# board.net
KiCad netlist of a schematic drawn in EAGLE
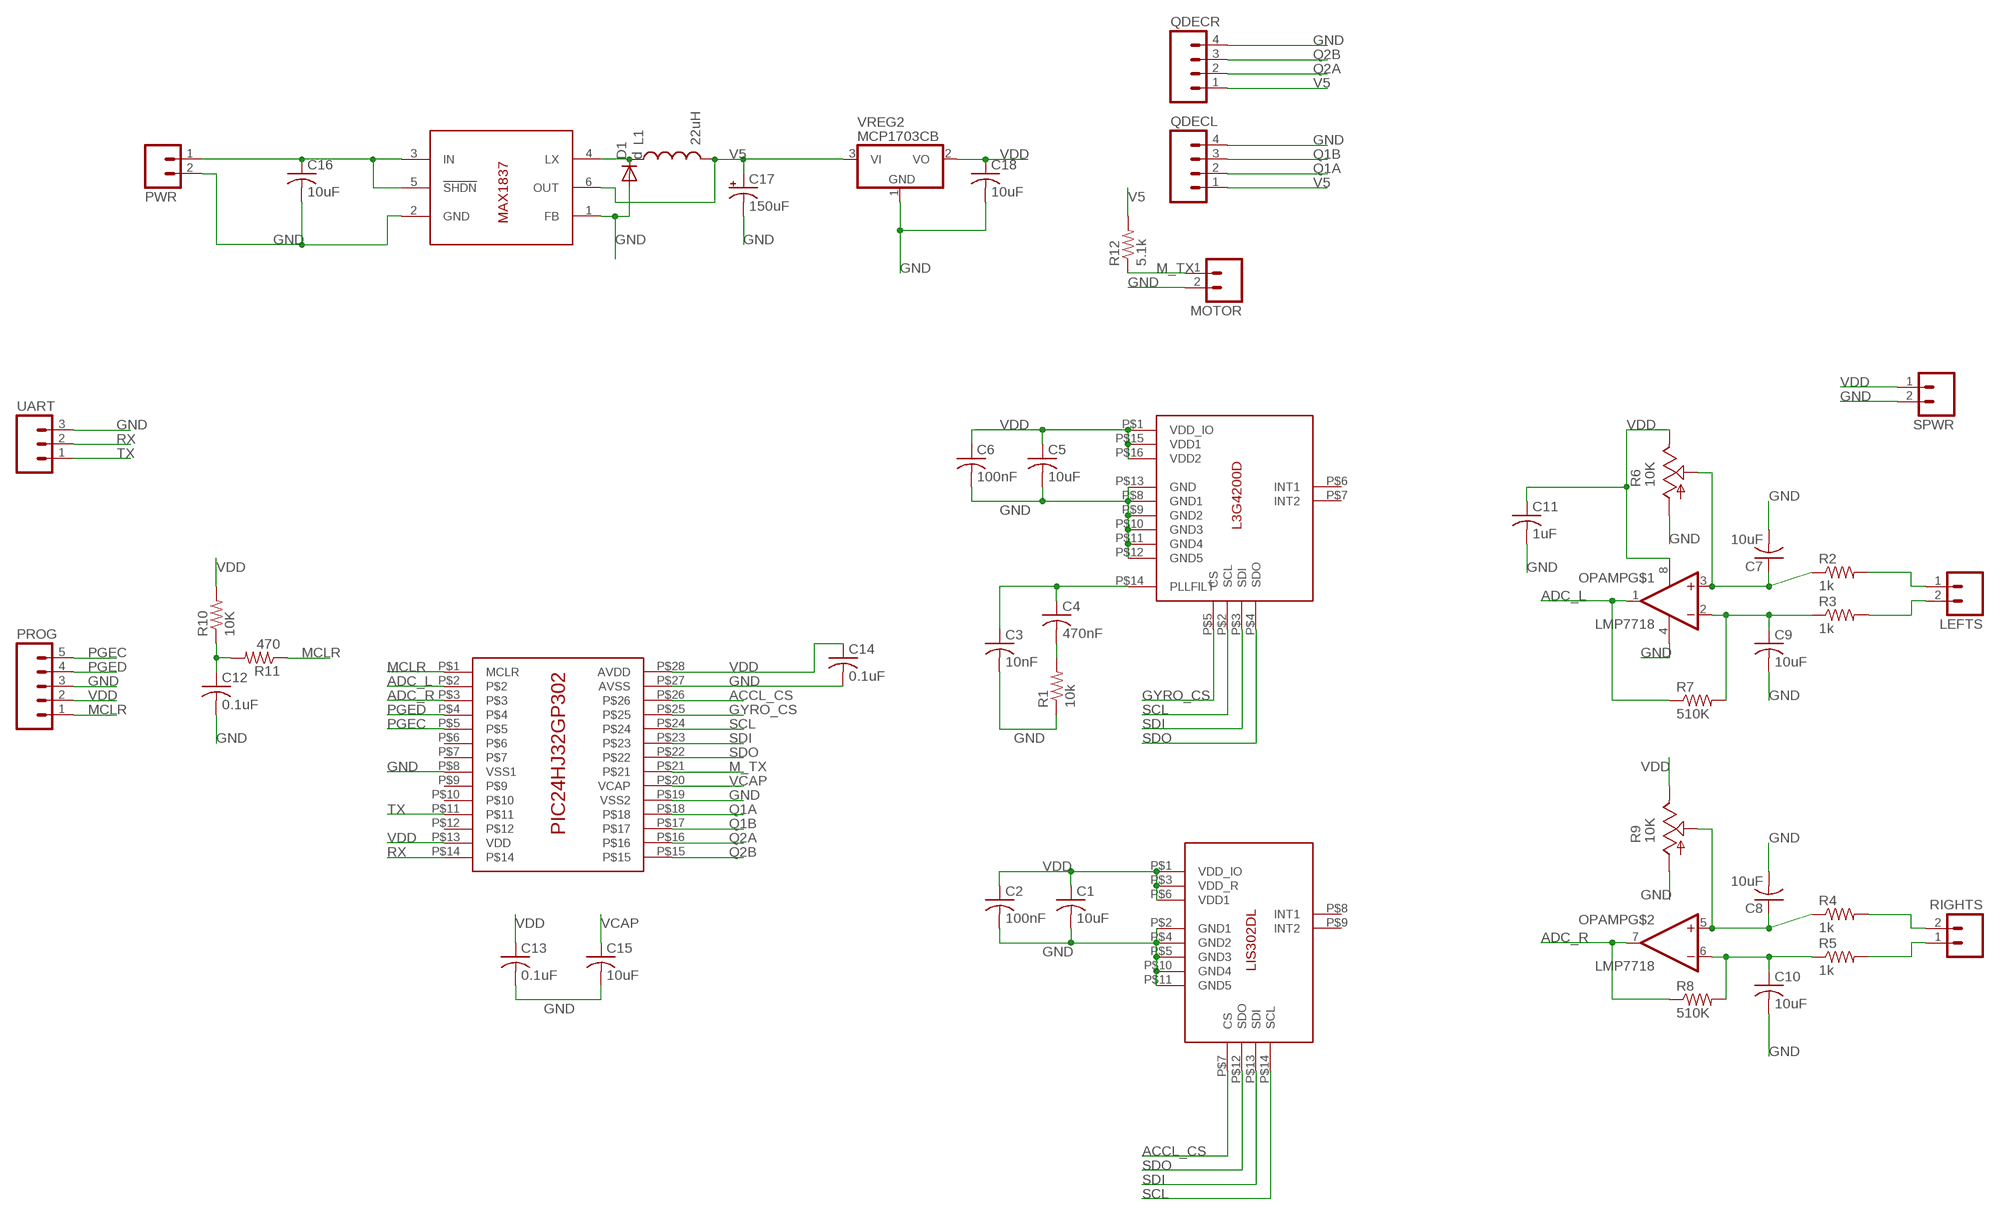
[diagram p0: schematic, sheet 1]

(export (version "E")
  (design (tool "Eeschema 10.0.6"))
  (components
    (comp (ref "C1")
      (value "10uF")
      (footprint "eagle-import:C0805")
      (libsource (lib "eagle-import") (part "C-USC0805"))
    )
    (comp (ref "C2")
      (value "100nF")
      (footprint "eagle-import:C0805")
      (libsource (lib "eagle-import") (part "C-USC0805"))
    )
    (comp (ref "C3")
      (value "10nF")
      (footprint "eagle-import:C0805")
      (libsource (lib "eagle-import") (part "C-USC0805"))
    )
    (comp (ref "C4")
      (value "470nF")
      (footprint "eagle-import:C0805")
      (libsource (lib "eagle-import") (part "C-USC0805"))
    )
    (comp (ref "C5")
      (value "10uF")
      (footprint "eagle-import:C0805")
      (libsource (lib "eagle-import") (part "C-USC0805"))
    )
    (comp (ref "C6")
      (value "100nF")
      (footprint "eagle-import:C0805")
      (libsource (lib "eagle-import") (part "C-USC0805"))
    )
    (comp (ref "C7")
      (value "10uF")
      (footprint "eagle-import:C1206")
      (libsource (lib "eagle-import") (part "C-USC1206"))
    )
    (comp (ref "C8")
      (value "10uF")
      (footprint "eagle-import:C1206")
      (libsource (lib "eagle-import") (part "C-USC1206"))
    )
    (comp (ref "C9")
      (value "10uF")
      (footprint "eagle-import:C1206")
      (libsource (lib "eagle-import") (part "C-USC1206"))
    )
    (comp (ref "C10")
      (value "10uF")
      (footprint "eagle-import:C1206")
      (libsource (lib "eagle-import") (part "C-USC1206"))
    )
    (comp (ref "C11")
      (value "1uF")
      (footprint "eagle-import:C0805")
      (libsource (lib "eagle-import") (part "C-USC0805"))
    )
    (comp (ref "C12")
      (value "0.1uF")
      (footprint "eagle-import:C0805")
      (libsource (lib "eagle-import") (part "C-USC0805"))
    )
    (comp (ref "C13")
      (value "0.1uF")
      (footprint "eagle-import:C0805")
      (libsource (lib "eagle-import") (part "C-USC0805"))
    )
    (comp (ref "C14")
      (value "0.1uF")
      (footprint "eagle-import:C0805")
      (libsource (lib "eagle-import") (part "C-USC0805"))
    )
    (comp (ref "C15")
      (value "10uF")
      (footprint "eagle-import:C0805")
      (libsource (lib "eagle-import") (part "C-USC0805"))
    )
    (comp (ref "C16")
      (value "10uF")
      (footprint "eagle-import:C1206")
      (libsource (lib "eagle-import") (part "C-USC1206"))
    )
    (comp (ref "C17")
      (value "150uF")
      (footprint "eagle-import:CT3528")
      (libsource (lib "eagle-import") (part "CPOL-USCT3528"))
    )
    (comp (ref "C18")
      (value "10uF")
      (footprint "eagle-import:C0805")
      (libsource (lib "eagle-import") (part "C-USC0805"))
    )
    (comp (ref "D1")
      (value "d")
      (footprint "eagle-import:SOD-323")
      (libsource (lib "eagle-import") (part "DIODESOD"))
    )
    (comp (ref "L1")
      (value "22uH")
      (footprint "eagle-import:1007")
      (libsource (lib "eagle-import") (part "INDUCTOR1007"))
    )
    (comp (ref "LEFTS")
      (value "M02POLAR")
      (footprint "eagle-import:MOLEX-1X2")
      (libsource (lib "eagle-import") (part "M02POLAR"))
    )
    (comp (ref "MOTOR")
      (value "M02POLAR")
      (footprint "eagle-import:MOLEX-1X2")
      (libsource (lib "eagle-import") (part "M02POLAR"))
    )
    (comp (ref "OPAMP")
      (value "LMP7718")
      (footprint "eagle-import:SO08")
      (libsource (lib "eagle-import") (part "LMP7718"))
    )
    (comp (ref "PROG")
      (value "M05PTH")
      (footprint "eagle-import:1X05")
      (libsource (lib "eagle-import") (part "M05PTH"))
    )
    (comp (ref "PWR")
      (value "M02POLAR")
      (footprint "eagle-import:MOLEX-1X2")
      (libsource (lib "eagle-import") (part "M02POLAR"))
    )
    (comp (ref "QDECL")
      (value "M04POLAR")
      (footprint "eagle-import:MOLEX-1X4")
      (libsource (lib "eagle-import") (part "M04POLAR"))
    )
    (comp (ref "QDECR")
      (value "M04POLAR")
      (footprint "eagle-import:MOLEX-1X4")
      (libsource (lib "eagle-import") (part "M04POLAR"))
    )
    (comp (ref "R1")
      (value "10k")
      (footprint "eagle-import:R0805")
      (libsource (lib "eagle-import") (part "R-US_R0805"))
    )
    (comp (ref "R2")
      (value "1k")
      (footprint "eagle-import:R1206")
      (libsource (lib "eagle-import") (part "R-US_R1206"))
    )
    (comp (ref "R3")
      (value "1k")
      (footprint "eagle-import:R1206")
      (libsource (lib "eagle-import") (part "R-US_R1206"))
    )
    (comp (ref "R4")
      (value "1k")
      (footprint "eagle-import:R1206")
      (libsource (lib "eagle-import") (part "R-US_R1206"))
    )
    (comp (ref "R5")
      (value "1k")
      (footprint "eagle-import:R1206")
      (libsource (lib "eagle-import") (part "R-US_R1206"))
    )
    (comp (ref "R6")
      (value "10K")
      (footprint "eagle-import:RJ6S")
      (libsource (lib "eagle-import") (part "TRIM_US-RJ6S"))
    )
    (comp (ref "R7")
      (value "510K")
      (footprint "eagle-import:R0805")
      (libsource (lib "eagle-import") (part "R-US_R0805"))
    )
    (comp (ref "R8")
      (value "510K")
      (footprint "eagle-import:R0805")
      (libsource (lib "eagle-import") (part "R-US_R0805"))
    )
    (comp (ref "R9")
      (value "10K")
      (footprint "eagle-import:RJ6S")
      (libsource (lib "eagle-import") (part "TRIM_US-RJ6S"))
    )
    (comp (ref "R10")
      (value "10K")
      (footprint "eagle-import:R0805")
      (libsource (lib "eagle-import") (part "R-US_R0805"))
    )
    (comp (ref "R11")
      (value "470")
      (footprint "eagle-import:R0805")
      (libsource (lib "eagle-import") (part "R-US_R0805"))
    )
    (comp (ref "R12")
      (value "5.1k")
      (footprint "eagle-import:R0805")
      (libsource (lib "eagle-import") (part "R-US_R0805"))
    )
    (comp (ref "RIGHTS")
      (value "M02POLAR")
      (footprint "eagle-import:MOLEX-1X2")
      (libsource (lib "eagle-import") (part "M02POLAR"))
    )
    (comp (ref "SPWR")
      (value "M02POLAR")
      (footprint "eagle-import:MOLEX-1X2")
      (libsource (lib "eagle-import") (part "M02POLAR"))
    )
    (comp (ref "U$1")
      (value "PIC24HJ32GP302")
      (footprint "eagle-import:SOIC-28")
      (libsource (lib "eagle-import") (part "PIC24HJ32GP302"))
    )
    (comp (ref "U$2")
      (value "L3G4200D")
      (footprint "eagle-import:LGA-16")
      (libsource (lib "eagle-import") (part "L3G4200D"))
    )
    (comp (ref "U$3")
      (value "LIS302DL")
      (footprint "eagle-import:LGA-14")
      (libsource (lib "eagle-import") (part "LIS302DL"))
    )
    (comp (ref "UART")
      (value "M03PTH")
      (footprint "eagle-import:1X03")
      (libsource (lib "eagle-import") (part "M03PTH"))
    )
    (comp (ref "VREG1")
      (value "MAX1837")
      (footprint "eagle-import:SOT23-6L")
      (libsource (lib "eagle-import") (part "MAX1837"))
    )
    (comp (ref "VREG2")
      (value "MCP1703CB")
      (footprint "eagle-import:SOT23")
      (libsource (lib "eagle-import") (part "MCP1703CB"))
    )
  )
  (nets
    (net (code "1") (name "/ACCL_CS") (class "Default")
      (node (ref "U$1") (pin "P$26") (pinfunction "P$26_P$26") (pintype "bidirectional"))
      (node (ref "U$3") (pin "P$7") (pinfunction "CS_P$7") (pintype "input"))
    )
    (net (code "2") (name "/ADC_L") (class "Default")
      (node (ref "OPAMP") (pin "1") (pinfunction "OUT_1") (pintype "output"))
      (node (ref "R7") (pin "1") (pinfunction "1_1") (pintype "passive"))
      (node (ref "U$1") (pin "P$2") (pinfunction "P$2_P$2") (pintype "bidirectional"))
    )
    (net (code "3") (name "/ADC_R") (class "Default")
      (node (ref "OPAMP") (pin "7") (pinfunction "OUT_7") (pintype "output"))
      (node (ref "R8") (pin "1") (pinfunction "1_1") (pintype "passive"))
      (node (ref "U$1") (pin "P$3") (pinfunction "P$3_P$3") (pintype "bidirectional"))
    )
    (net (code "4") (name "/GND") (class "Default")
      (node (ref "C1") (pin "2") (pinfunction "2_2") (pintype "passive"))
      (node (ref "C10") (pin "2") (pinfunction "2_2") (pintype "passive"))
      (node (ref "C11") (pin "2") (pinfunction "2_2") (pintype "passive"))
      (node (ref "C12") (pin "2") (pinfunction "2_2") (pintype "passive"))
      (node (ref "C13") (pin "2") (pinfunction "2_2") (pintype "passive"))
      (node (ref "C14") (pin "2") (pinfunction "2_2") (pintype "passive"))
      (node (ref "C15") (pin "2") (pinfunction "2_2") (pintype "passive"))
      (node (ref "C16") (pin "2") (pinfunction "2_2") (pintype "passive"))
      (node (ref "C17") (pin "-") (pinfunction "-_-") (pintype "passive"))
      (node (ref "C18") (pin "2") (pinfunction "2_2") (pintype "passive"))
      (node (ref "C2") (pin "2") (pinfunction "2_2") (pintype "passive"))
      (node (ref "C3") (pin "2") (pinfunction "2_2") (pintype "passive"))
      (node (ref "C5") (pin "2") (pinfunction "2_2") (pintype "passive"))
      (node (ref "C6") (pin "2") (pinfunction "2_2") (pintype "passive"))
      (node (ref "C7") (pin "2") (pinfunction "2_2") (pintype "passive"))
      (node (ref "C8") (pin "2") (pinfunction "2_2") (pintype "passive"))
      (node (ref "C9") (pin "2") (pinfunction "2_2") (pintype "passive"))
      (node (ref "D1") (pin "2") (pinfunction "A_2") (pintype "passive"))
      (node (ref "MOTOR") (pin "2") (pinfunction "2_2") (pintype "passive"))
      (node (ref "OPAMP") (pin "4") (pinfunction "V-_4") (pintype "power_in"))
      (node (ref "PROG") (pin "3") (pinfunction "3_3") (pintype "passive"))
      (node (ref "PWR") (pin "2") (pinfunction "2_2") (pintype "passive"))
      (node (ref "QDECL") (pin "4") (pinfunction "4_4") (pintype "passive"))
      (node (ref "QDECR") (pin "4") (pinfunction "4_4") (pintype "passive"))
      (node (ref "R1") (pin "1") (pinfunction "1_1") (pintype "passive"))
      (node (ref "R6") (pin "A") (pinfunction "A_A") (pintype "passive"))
      (node (ref "R9") (pin "A") (pinfunction "A_A") (pintype "passive"))
      (node (ref "SPWR") (pin "2") (pinfunction "2_2") (pintype "passive"))
      (node (ref "U$1") (pin "P$19") (pinfunction "VSS2_P$19") (pintype "power_in"))
      (node (ref "U$1") (pin "P$27") (pinfunction "AVSS_P$27") (pintype "power_in"))
      (node (ref "U$1") (pin "P$8") (pinfunction "VSS1_P$8") (pintype "power_in"))
      (node (ref "U$2") (pin "P$10") (pinfunction "GND3_P$10") (pintype "power_in"))
      (node (ref "U$2") (pin "P$11") (pinfunction "GND4_P$11") (pintype "power_in"))
      (node (ref "U$2") (pin "P$12") (pinfunction "GND5_P$12") (pintype "power_in"))
      (node (ref "U$2") (pin "P$13") (pinfunction "GND_P$13") (pintype "power_in"))
      (node (ref "U$2") (pin "P$8") (pinfunction "GND1_P$8") (pintype "power_in"))
      (node (ref "U$2") (pin "P$9") (pinfunction "GND2_P$9") (pintype "power_in"))
      (node (ref "U$3") (pin "P$10") (pinfunction "GND4_P$10") (pintype "power_in"))
      (node (ref "U$3") (pin "P$11") (pinfunction "GND5_P$11") (pintype "power_in"))
      (node (ref "U$3") (pin "P$2") (pinfunction "GND1_P$2") (pintype "power_in"))
      (node (ref "U$3") (pin "P$4") (pinfunction "GND2_P$4") (pintype "power_in"))
      (node (ref "U$3") (pin "P$5") (pinfunction "GND3_P$5") (pintype "power_in"))
      (node (ref "UART") (pin "3") (pinfunction "3_3") (pintype "passive"))
      (node (ref "VREG1") (pin "1") (pinfunction "FB_1") (pintype "input"))
      (node (ref "VREG1") (pin "2") (pinfunction "GND_2") (pintype "power_in"))
      (node (ref "VREG2") (pin "1") (pinfunction "GND_1") (pintype "passive"))
    )
    (net (code "5") (name "/GYRO_CS") (class "Default")
      (node (ref "U$1") (pin "P$25") (pinfunction "P$25_P$25") (pintype "bidirectional"))
      (node (ref "U$2") (pin "P$5") (pinfunction "CS_P$5") (pintype "input"))
    )
    (net (code "6") (name "/MCLR") (class "Default")
      (node (ref "PROG") (pin "1") (pinfunction "1_1") (pintype "passive"))
      (node (ref "R11") (pin "1") (pinfunction "1_1") (pintype "passive"))
      (node (ref "U$1") (pin "P$1") (pinfunction "MCLR_P$1") (pintype "input"))
    )
    (net (code "7") (name "/M_TX") (class "Default")
      (node (ref "MOTOR") (pin "1") (pinfunction "1_1") (pintype "passive"))
      (node (ref "R12") (pin "1") (pinfunction "1_1") (pintype "passive"))
      (node (ref "U$1") (pin "P$21") (pinfunction "P$21_P$21") (pintype "bidirectional"))
    )
    (net (code "8") (name "/PGEC") (class "Default")
      (node (ref "PROG") (pin "5") (pinfunction "5_5") (pintype "passive"))
      (node (ref "U$1") (pin "P$5") (pinfunction "P$5_P$5") (pintype "bidirectional"))
    )
    (net (code "9") (name "/PGED") (class "Default")
      (node (ref "PROG") (pin "4") (pinfunction "4_4") (pintype "passive"))
      (node (ref "U$1") (pin "P$4") (pinfunction "P$4_P$4") (pintype "bidirectional"))
    )
    (net (code "10") (name "/Q1A") (class "Default")
      (node (ref "QDECL") (pin "2") (pinfunction "2_2") (pintype "passive"))
      (node (ref "U$1") (pin "P$18") (pinfunction "P$18_P$18") (pintype "bidirectional"))
    )
    (net (code "11") (name "/Q1B") (class "Default")
      (node (ref "QDECL") (pin "3") (pinfunction "3_3") (pintype "passive"))
      (node (ref "U$1") (pin "P$17") (pinfunction "P$17_P$17") (pintype "bidirectional"))
    )
    (net (code "12") (name "/Q2A") (class "Default")
      (node (ref "QDECR") (pin "2") (pinfunction "2_2") (pintype "passive"))
      (node (ref "U$1") (pin "P$16") (pinfunction "P$16_P$16") (pintype "bidirectional"))
    )
    (net (code "13") (name "/Q2B") (class "Default")
      (node (ref "QDECR") (pin "3") (pinfunction "3_3") (pintype "passive"))
      (node (ref "U$1") (pin "P$15") (pinfunction "P$15_P$15") (pintype "bidirectional"))
    )
    (net (code "14") (name "/RX") (class "Default")
      (node (ref "U$1") (pin "P$14") (pinfunction "P$14_P$14") (pintype "bidirectional"))
      (node (ref "UART") (pin "2") (pinfunction "2_2") (pintype "passive"))
    )
    (net (code "15") (name "/SCL") (class "Default")
      (node (ref "U$1") (pin "P$24") (pinfunction "P$24_P$24") (pintype "bidirectional"))
      (node (ref "U$2") (pin "P$2") (pinfunction "SCL_P$2") (pintype "input"))
      (node (ref "U$3") (pin "P$14") (pinfunction "SCL_P$14") (pintype "input"))
    )
    (net (code "16") (name "/SDI") (class "Default")
      (node (ref "U$1") (pin "P$23") (pinfunction "P$23_P$23") (pintype "bidirectional"))
      (node (ref "U$2") (pin "P$3") (pinfunction "SDI_P$3") (pintype "input"))
      (node (ref "U$3") (pin "P$13") (pinfunction "SDI_P$13") (pintype "bidirectional"))
    )
    (net (code "17") (name "/SDO") (class "Default")
      (node (ref "U$1") (pin "P$22") (pinfunction "P$22_P$22") (pintype "bidirectional"))
      (node (ref "U$2") (pin "P$4") (pinfunction "SDO_P$4") (pintype "output"))
      (node (ref "U$3") (pin "P$12") (pinfunction "SDO_P$12") (pintype "output"))
    )
    (net (code "18") (name "/TX") (class "Default")
      (node (ref "U$1") (pin "P$11") (pinfunction "P$11_P$11") (pintype "bidirectional"))
      (node (ref "UART") (pin "1") (pinfunction "1_1") (pintype "passive"))
    )
    (net (code "19") (name "/V5") (class "Default")
      (node (ref "C17") (pin "+") (pinfunction "+_+") (pintype "passive"))
      (node (ref "L1") (pin "2") (pinfunction "2_2") (pintype "passive"))
      (node (ref "QDECL") (pin "1") (pinfunction "1_1") (pintype "passive"))
      (node (ref "QDECR") (pin "1") (pinfunction "1_1") (pintype "passive"))
      (node (ref "R12") (pin "2") (pinfunction "2_2") (pintype "passive"))
      (node (ref "VREG1") (pin "6") (pinfunction "OUT_6") (pintype "input"))
      (node (ref "VREG2") (pin "3") (pinfunction "VI_3") (pintype "input"))
    )
    (net (code "20") (name "/VCAP") (class "Default")
      (node (ref "C15") (pin "1") (pinfunction "1_1") (pintype "passive"))
      (node (ref "U$1") (pin "P$20") (pinfunction "VCAP_P$20") (pintype "power_in"))
    )
    (net (code "21") (name "/VDD") (class "Default")
      (node (ref "C1") (pin "1") (pinfunction "1_1") (pintype "passive"))
      (node (ref "C11") (pin "1") (pinfunction "1_1") (pintype "passive"))
      (node (ref "C13") (pin "1") (pinfunction "1_1") (pintype "passive"))
      (node (ref "C14") (pin "1") (pinfunction "1_1") (pintype "passive"))
      (node (ref "C18") (pin "1") (pinfunction "1_1") (pintype "passive"))
      (node (ref "C2") (pin "1") (pinfunction "1_1") (pintype "passive"))
      (node (ref "C5") (pin "1") (pinfunction "1_1") (pintype "passive"))
      (node (ref "C6") (pin "1") (pinfunction "1_1") (pintype "passive"))
      (node (ref "OPAMP") (pin "8") (pinfunction "V+_8") (pintype "power_in"))
      (node (ref "PROG") (pin "2") (pinfunction "2_2") (pintype "passive"))
      (node (ref "R10") (pin "2") (pinfunction "2_2") (pintype "passive"))
      (node (ref "R6") (pin "E") (pinfunction "E_E") (pintype "passive"))
      (node (ref "R9") (pin "E") (pinfunction "E_E") (pintype "passive"))
      (node (ref "SPWR") (pin "1") (pinfunction "1_1") (pintype "passive"))
      (node (ref "U$1") (pin "P$13") (pinfunction "VDD_P$13") (pintype "power_in"))
      (node (ref "U$1") (pin "P$28") (pinfunction "AVDD_P$28") (pintype "power_in"))
      (node (ref "U$2") (pin "P$1") (pinfunction "VDD_IO_P$1") (pintype "power_in"))
      (node (ref "U$2") (pin "P$15") (pinfunction "VDD1_P$15") (pintype "power_in"))
      (node (ref "U$2") (pin "P$16") (pinfunction "VDD2_P$16") (pintype "power_in"))
      (node (ref "U$3") (pin "P$1") (pinfunction "VDD_IO_P$1") (pintype "power_in"))
      (node (ref "U$3") (pin "P$3") (pinfunction "VDD_R_P$3") (pintype "power_in"))
      (node (ref "U$3") (pin "P$6") (pinfunction "VDD1_P$6") (pintype "power_in"))
      (node (ref "VREG2") (pin "2") (pinfunction "VO_2") (pintype "passive"))
    )
    (net (code "22") (name "Net-(C4-Pad2)") (class "Default")
      (node (ref "C4") (pin "2") (pinfunction "2_2") (pintype "passive"))
      (node (ref "R1") (pin "2") (pinfunction "2_2") (pintype "passive"))
    )
    (net (code "23") (name "Net-(C12-Pad1)") (class "Default")
      (node (ref "C12") (pin "1") (pinfunction "1_1") (pintype "passive"))
      (node (ref "R10") (pin "1") (pinfunction "1_1") (pintype "passive"))
      (node (ref "R11") (pin "2") (pinfunction "2_2") (pintype "passive"))
    )
    (net (code "24") (name "Net-(D1-C)") (class "Default")
      (node (ref "D1") (pin "1") (pinfunction "C_1") (pintype "passive"))
      (node (ref "L1") (pin "1") (pinfunction "1_1") (pintype "passive"))
      (node (ref "VREG1") (pin "4") (pinfunction "LX_4") (pintype "power_in"))
    )
    (net (code "25") (name "Net-(LEFTS-Pad1)") (class "Default")
      (node (ref "LEFTS") (pin "1") (pinfunction "1_1") (pintype "passive"))
      (node (ref "R2") (pin "2") (pinfunction "2_2") (pintype "passive"))
    )
    (net (code "26") (name "Net-(LEFTS-Pad2)") (class "Default")
      (node (ref "LEFTS") (pin "2") (pinfunction "2_2") (pintype "passive"))
      (node (ref "R3") (pin "2") (pinfunction "2_2") (pintype "passive"))
    )
    (net (code "27") (name "Net-(OPAMPA-+IN)") (class "Default")
      (node (ref "C7") (pin "1") (pinfunction "1_1") (pintype "passive"))
      (node (ref "OPAMP") (pin "3") (pinfunction "+IN_3") (pintype "input"))
      (node (ref "R2") (pin "1") (pinfunction "1_1") (pintype "passive"))
      (node (ref "R6") (pin "S") (pinfunction "S_S") (pintype "passive"))
    )
    (net (code "28") (name "Net-(OPAMPA--IN)") (class "Default")
      (node (ref "C9") (pin "1") (pinfunction "1_1") (pintype "passive"))
      (node (ref "OPAMP") (pin "2") (pinfunction "-IN_2") (pintype "input"))
      (node (ref "R3") (pin "1") (pinfunction "1_1") (pintype "passive"))
      (node (ref "R7") (pin "2") (pinfunction "2_2") (pintype "passive"))
    )
    (net (code "29") (name "Net-(OPAMPB-+IN)") (class "Default")
      (node (ref "C8") (pin "1") (pinfunction "1_1") (pintype "passive"))
      (node (ref "OPAMP") (pin "5") (pinfunction "+IN_5") (pintype "input"))
      (node (ref "R4") (pin "1") (pinfunction "1_1") (pintype "passive"))
      (node (ref "R9") (pin "S") (pinfunction "S_S") (pintype "passive"))
    )
    (net (code "30") (name "Net-(OPAMPB--IN)") (class "Default")
      (node (ref "C10") (pin "1") (pinfunction "1_1") (pintype "passive"))
      (node (ref "OPAMP") (pin "6") (pinfunction "-IN_6") (pintype "input"))
      (node (ref "R5") (pin "1") (pinfunction "1_1") (pintype "passive"))
      (node (ref "R8") (pin "2") (pinfunction "2_2") (pintype "passive"))
    )
    (net (code "31") (name "Net-(R4-Pad2)") (class "Default")
      (node (ref "R4") (pin "2") (pinfunction "2_2") (pintype "passive"))
      (node (ref "RIGHTS") (pin "2") (pinfunction "2_2") (pintype "passive"))
    )
    (net (code "32") (name "Net-(R5-Pad2)") (class "Default")
      (node (ref "R5") (pin "2") (pinfunction "2_2") (pintype "passive"))
      (node (ref "RIGHTS") (pin "1") (pinfunction "1_1") (pintype "passive"))
    )
    (net (code "33") (name "Net-(U$2-PLLFILT)") (class "Default")
      (node (ref "C3") (pin "1") (pinfunction "1_1") (pintype "passive"))
      (node (ref "C4") (pin "1") (pinfunction "1_1") (pintype "passive"))
      (node (ref "U$2") (pin "P$14") (pinfunction "PLLFILT_P$14") (pintype "bidirectional"))
    )
    (net (code "34") (name "Net-(VREG1-IN)") (class "Default")
      (node (ref "C16") (pin "1") (pinfunction "1_1") (pintype "passive"))
      (node (ref "PWR") (pin "1") (pinfunction "1_1") (pintype "passive"))
      (node (ref "VREG1") (pin "3") (pinfunction "IN_3") (pintype "power_in"))
      (node (ref "VREG1") (pin "5") (pinfunction "~{SHDN}_5") (pintype "input"))
    )
    (net (code "35") (name "unconnected-(U$1-PadP$6)") (class "Default")
      (node (ref "U$1") (pin "P$6") (pinfunction "P$6_P$6") (pintype "bidirectional"))
    )
    (net (code "36") (name "unconnected-(U$1-PadP$7)") (class "Default")
      (node (ref "U$1") (pin "P$7") (pinfunction "P$7_P$7") (pintype "bidirectional"))
    )
    (net (code "37") (name "unconnected-(U$1-PadP$9)") (class "Default")
      (node (ref "U$1") (pin "P$9") (pinfunction "P$9_P$9") (pintype "bidirectional"))
    )
    (net (code "38") (name "unconnected-(U$1-PadP$10)") (class "Default")
      (node (ref "U$1") (pin "P$10") (pinfunction "P$10_P$10") (pintype "bidirectional"))
    )
    (net (code "39") (name "unconnected-(U$1-PadP$12)") (class "Default")
      (node (ref "U$1") (pin "P$12") (pinfunction "P$12_P$12") (pintype "bidirectional"))
    )
    (net (code "40") (name "unconnected-(U$2-INT1-PadP$6)") (class "Default")
      (node (ref "U$2") (pin "P$6") (pinfunction "INT1_P$6") (pintype "output"))
    )
    (net (code "41") (name "unconnected-(U$2-INT2-PadP$7)") (class "Default")
      (node (ref "U$2") (pin "P$7") (pinfunction "INT2_P$7") (pintype "output"))
    )
    (net (code "42") (name "unconnected-(U$3-INT1-PadP$8)") (class "Default")
      (node (ref "U$3") (pin "P$8") (pinfunction "INT1_P$8") (pintype "output"))
    )
    (net (code "43") (name "unconnected-(U$3-INT2-PadP$9)") (class "Default")
      (node (ref "U$3") (pin "P$9") (pinfunction "INT2_P$9") (pintype "output"))
    )
  )
)
